# Sensor-line.net
KiCad netlist of a schematic drawn in EAGLE
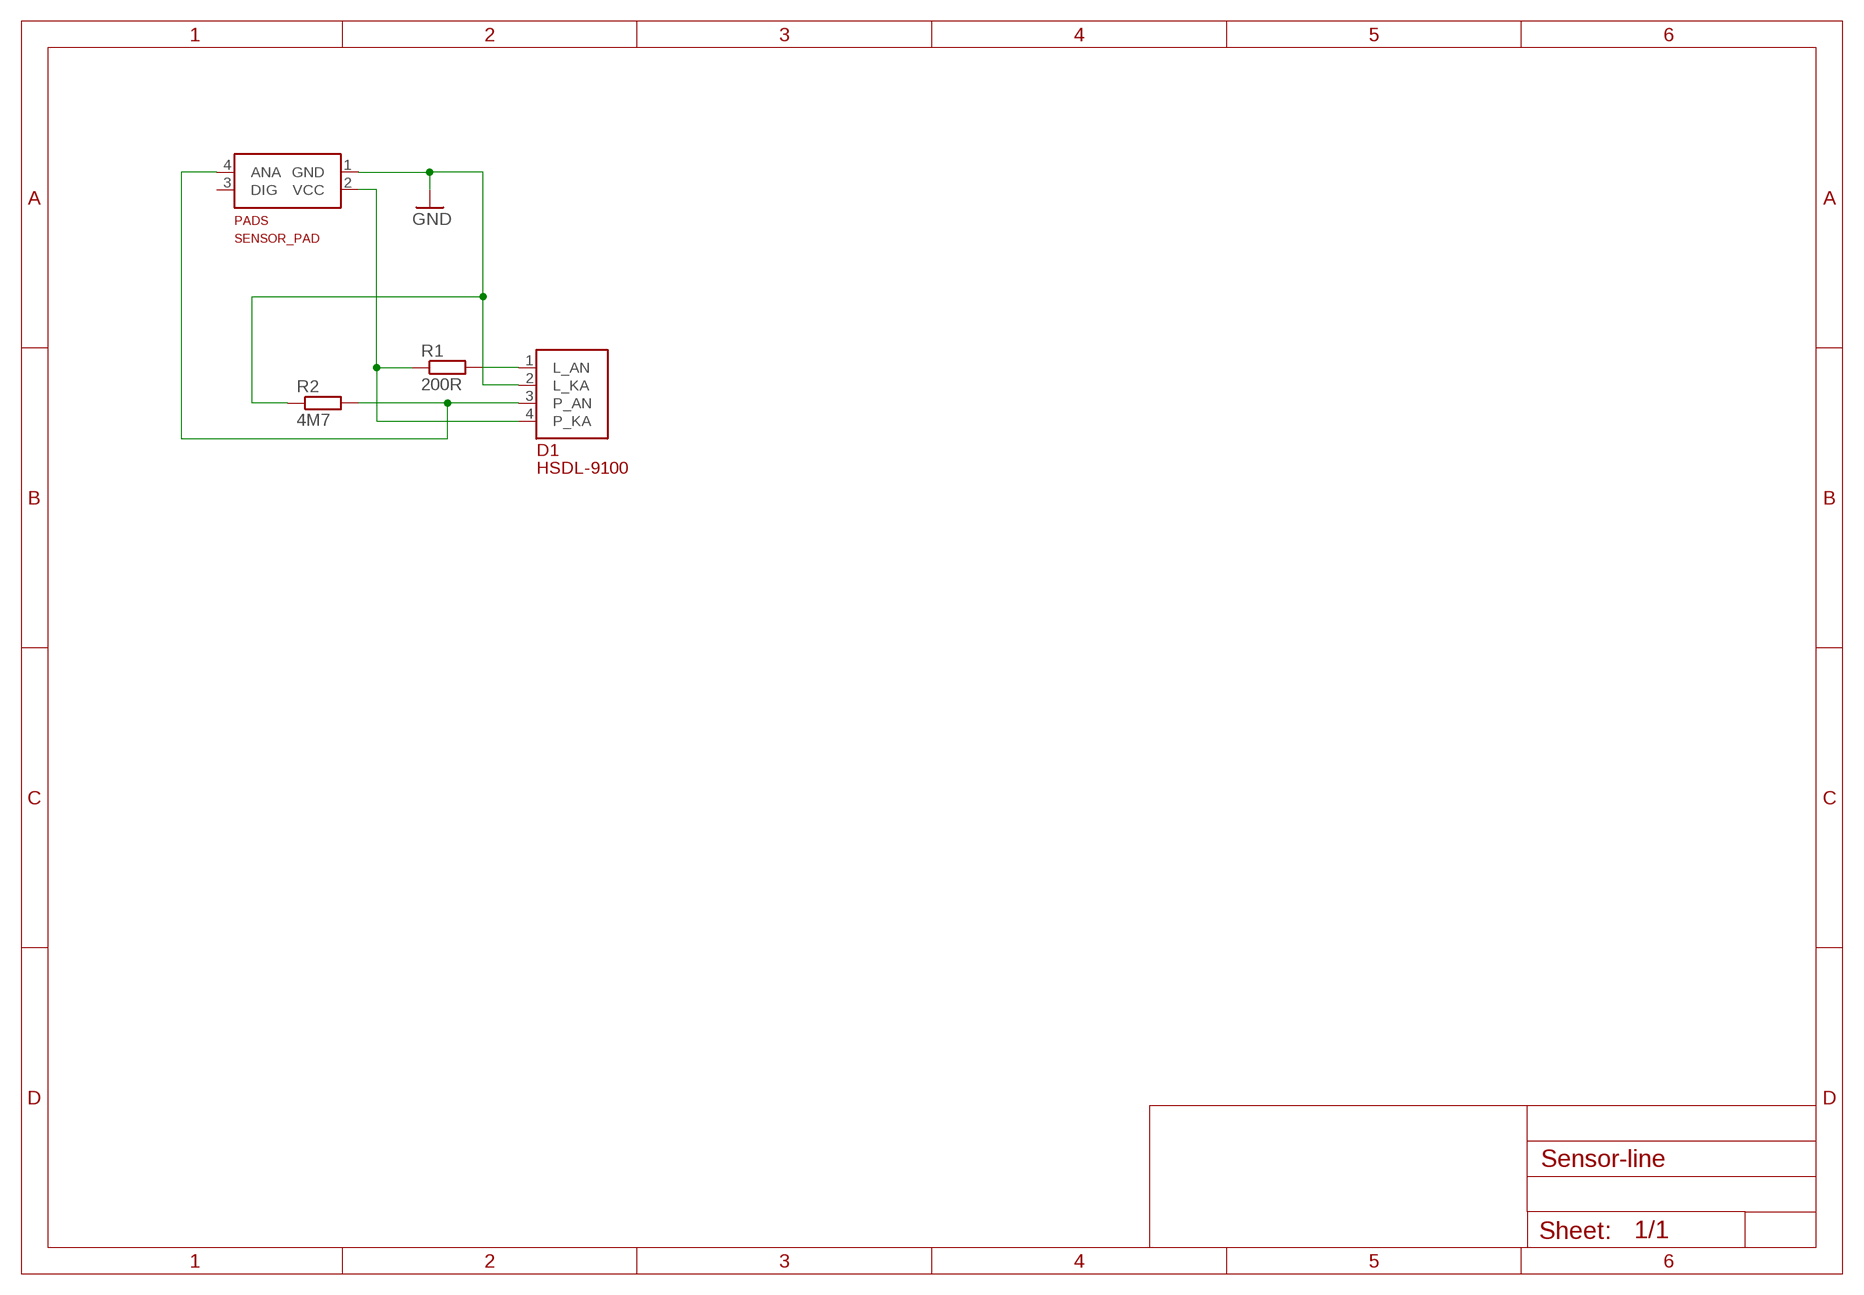
[diagram p0: schematic, sheet 1]

(export (version "E")
  (design (tool "Eeschema 10.0.6"))
  (components
    (comp (ref "D1")
      (value "HSDL-9100")
      (footprint "eagle-import:HSDL-9100")
      (fields (field (name "MF") "AVAGO TECHNOLOGIES") (field (name "MPN") "HSDL-9100-021"))
      (libsource (lib "eagle-import") (part "HSDL-9100"))
    )
    (comp (ref "PADS")
      (value "SENSOR_PAD")
      (footprint "eagle-import:SENSOR_PAD")
      (libsource (lib "eagle-import") (part "SENSOR_PAD"))
    )
    (comp (ref "R1")
      (value "200R")
      (footprint "eagle-import:R1206")
      (fields (field (name "MF") "PANASONIC ELECTRONIC COMPONENTS") (field (name "MPN") "ERJ8ENF2000V"))
      (libsource (lib "eagle-import") (part "R-EU_R1206"))
    )
    (comp (ref "R2")
      (value "4M7")
      (footprint "eagle-import:R0805")
      (fields (field (name "MF") "WELWYN") (field (name "MPN") "ASC0805-4M7FT5"))
      (libsource (lib "eagle-import") (part "R-EU_R0805"))
    )
  )
  (nets
    (net (code "1") (name "GND") (class "Default")
      (node (ref "D1") (pin "2") (pinfunction "L_KA_2") (pintype "bidirectional"))
      (node (ref "PADS") (pin "1") (pinfunction "GND_1") (pintype "bidirectional"))
      (node (ref "R2") (pin "1") (pinfunction "1_1") (pintype "passive"))
    )
    (net (code "2") (name "Net-(D1-L_AN)") (class "Default")
      (node (ref "D1") (pin "1") (pinfunction "L_AN_1") (pintype "bidirectional"))
      (node (ref "R1") (pin "2") (pinfunction "2_2") (pintype "passive"))
    )
    (net (code "3") (name "Net-(D1-P_AN)") (class "Default")
      (node (ref "D1") (pin "3") (pinfunction "P_AN_3") (pintype "bidirectional"))
      (node (ref "PADS") (pin "4") (pinfunction "ANA_4") (pintype "bidirectional"))
      (node (ref "R2") (pin "2") (pinfunction "2_2") (pintype "passive"))
    )
    (net (code "4") (name "Net-(D1-P_KA)") (class "Default")
      (node (ref "D1") (pin "4") (pinfunction "P_KA_4") (pintype "bidirectional"))
      (node (ref "PADS") (pin "2") (pinfunction "VCC_2") (pintype "bidirectional"))
      (node (ref "R1") (pin "1") (pinfunction "1_1") (pintype "passive"))
    )
    (net (code "5") (name "unconnected-(PADS-DIG-Pad3)") (class "Default")
      (node (ref "PADS") (pin "3") (pinfunction "DIG_3") (pintype "bidirectional"))
    )
  )
)
